# AY_Amp.net
KiCad netlist of a schematic drawn in Altium Designer
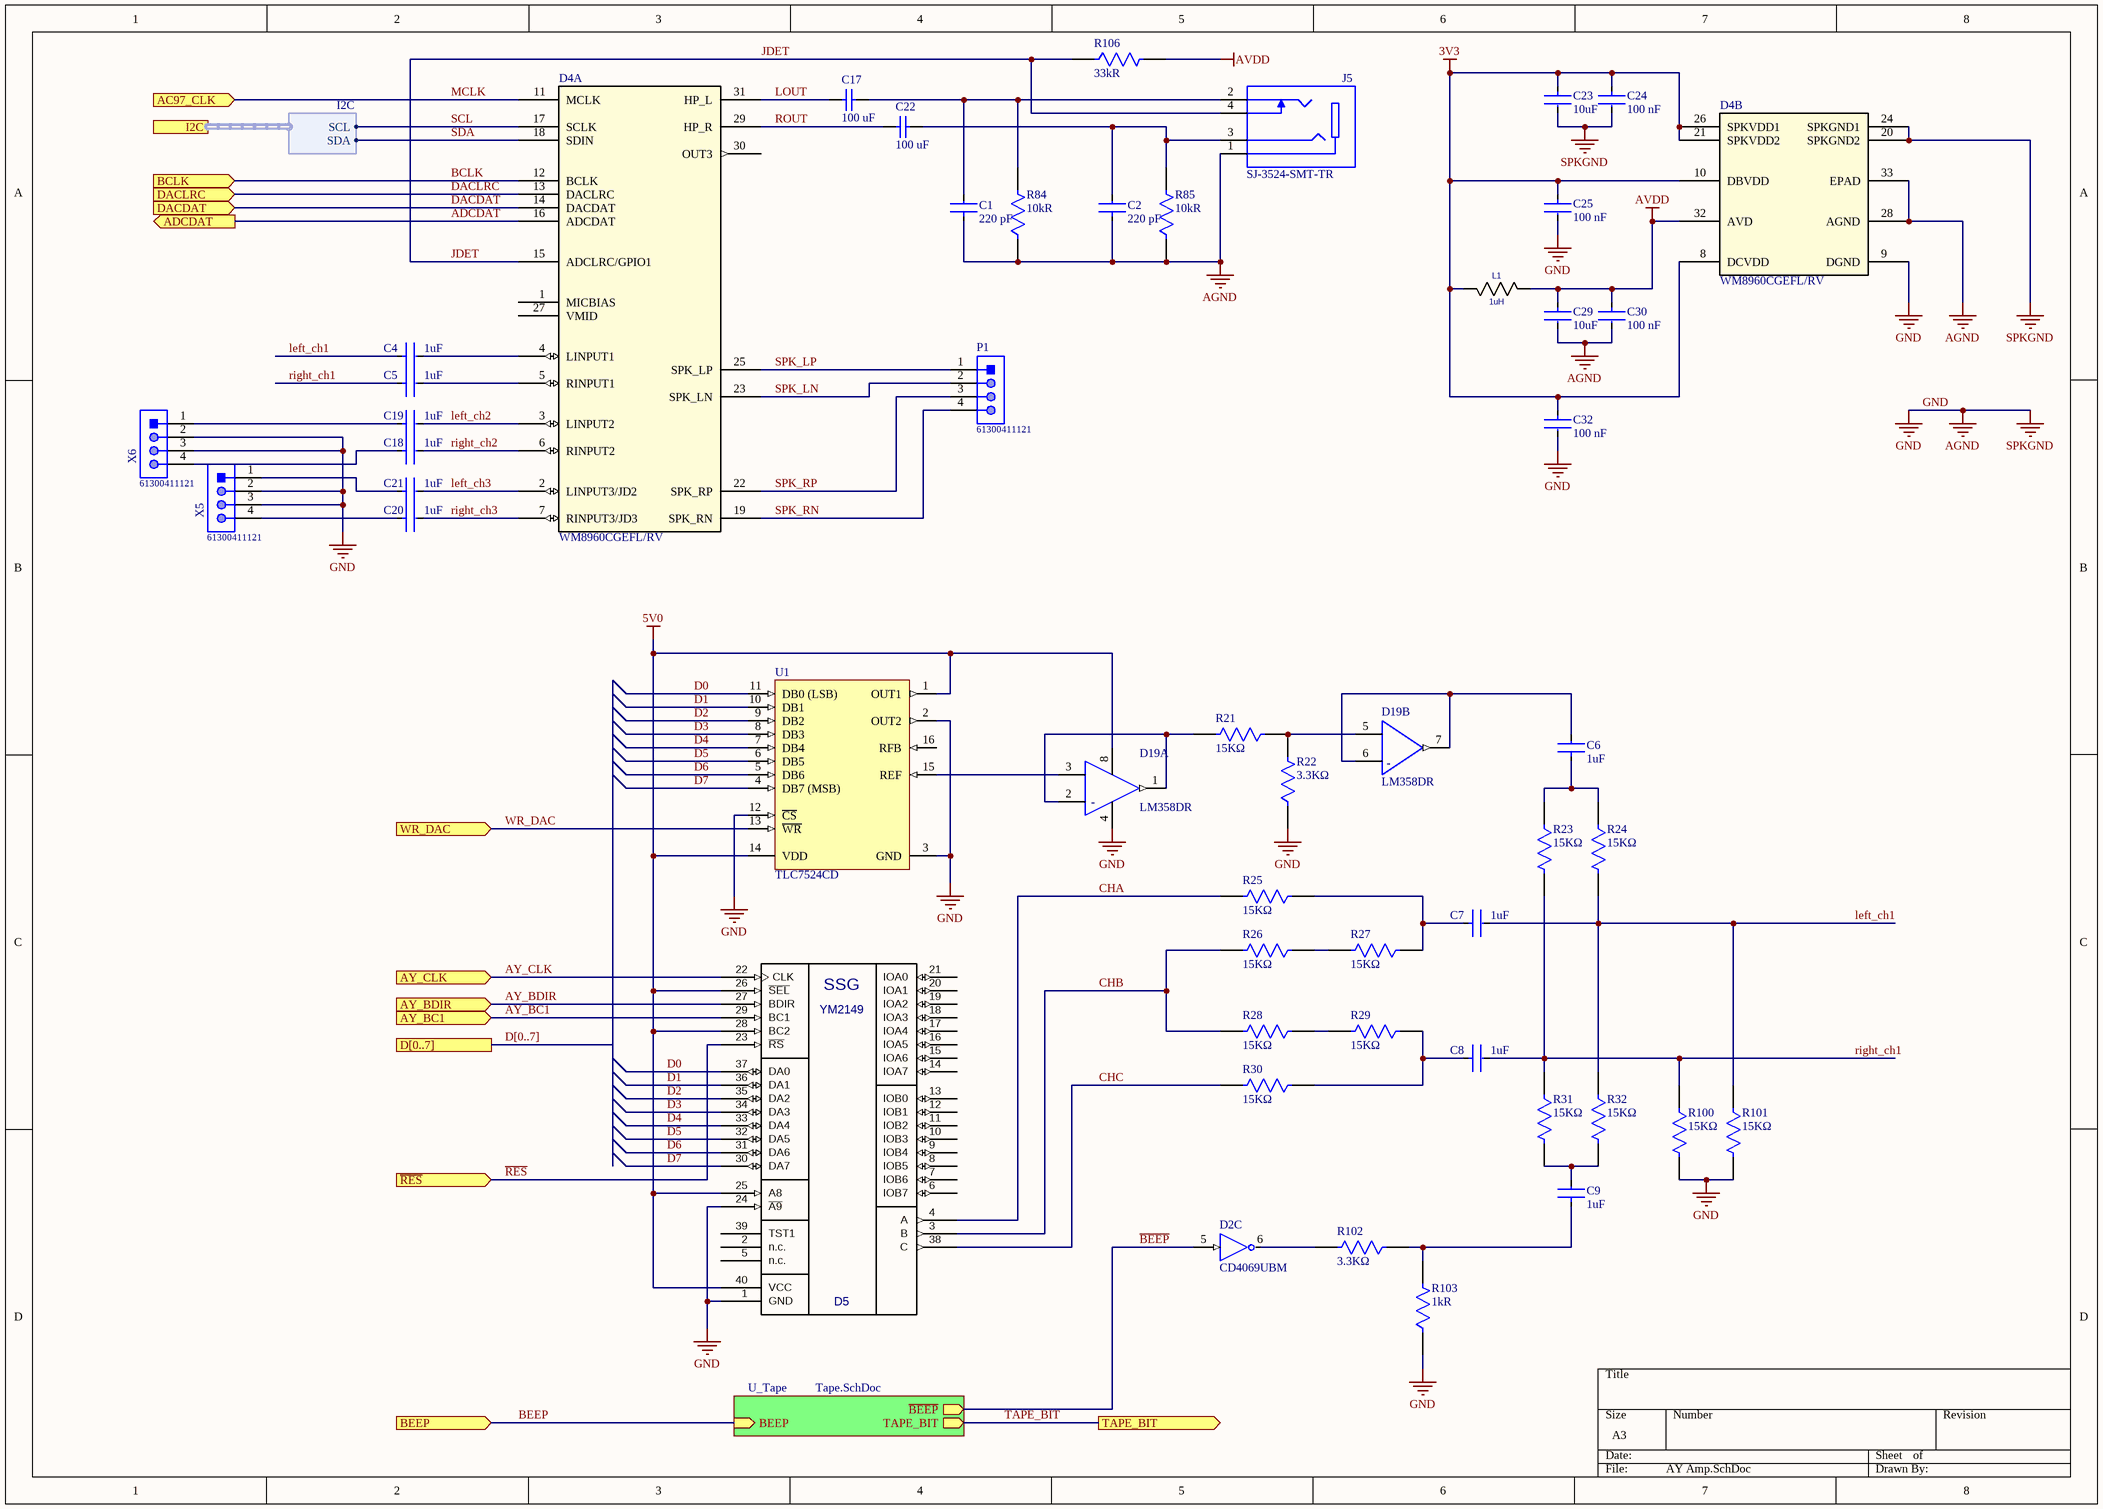
[diagram p0: AY Amp.SchDoc]

(export (version "E")
  (design (tool "Eeschema 10.0.6"))
  (components
    (comp (ref "C1")
      (value "CC0805KRX7R9BB221")
      (footprint "FP-CC0805-0_85-IPC_A")
      (description "CAP CER 220PF 50V X7R 0805")
      (fields
        (field (name "MANUFACTURER PART NUMBER") "VJ0805A221KXAPW1BC")
        (field (name "CAPACITANCE") "220 pF")
        (field (name "MANUFACTURER") "Vishay Vitramon")
      )
      (libsource (lib "SchLib") (part "CMP-1036-02315-3"))
    )
    (comp (ref "C2")
      (value "CC0805KRX7R9BB221")
      (footprint "FP-CC0805-0_85-IPC_A")
      (description "CAP CER 220PF 50V X7R 0805")
      (fields
        (field (name "MANUFACTURER PART NUMBER") "VJ0805A221KXAPW1BC")
        (field (name "CAPACITANCE") "220 pF")
        (field (name "MANUFACTURER") "Vishay Vitramon")
      )
      (libsource (lib "SchLib") (part "CMP-1036-02315-3"))
    )
    (comp (ref "C4")
      (value "GCM21BR71E105KA56L")
      (footprint "FP-GCM21B-0_15-IPC_A")
      (description "Ceramic Capacitor for Automotive 1uF ±10% 25VDC X7R 0805 Embossed T/R")
      (fields (field (name "CAPACITANCE") "1uF") (field (name "MANUFACTURER") "Murata"))
      (libsource (lib "SchLib") (part "CMP-2007-03346-2"))
    )
    (comp (ref "C5")
      (value "GCM21BR71E105KA56L")
      (footprint "FP-GCM21B-0_15-IPC_A")
      (description "Ceramic Capacitor for Automotive 1uF ±10% 25VDC X7R 0805 Embossed T/R")
      (fields (field (name "CAPACITANCE") "1uF") (field (name "MANUFACTURER") "Murata"))
      (libsource (lib "SchLib") (part "CMP-2007-03346-2"))
    )
    (comp (ref "C6")
      (value "GCM21BR71E105KA56L")
      (footprint "FP-GCM21B-0_15-IPC_A")
      (description "Ceramic Capacitor for Automotive 1uF ±10% 25VDC X7R 0805 Embossed T/R")
      (fields (field (name "CAPACITANCE") "1uF") (field (name "MANUFACTURER") "Murata"))
      (libsource (lib "SchLib") (part "CMP-2007-03346-2"))
    )
    (comp (ref "C7")
      (value "GCM21BR71E105KA56L")
      (footprint "FP-GCM21B-0_15-IPC_A")
      (description "Ceramic Capacitor for Automotive 1uF ±10% 25VDC X7R 0805 Embossed T/R")
      (fields (field (name "CAPACITANCE") "1uF") (field (name "MANUFACTURER") "Murata"))
      (libsource (lib "SchLib") (part "CMP-2007-03346-2"))
    )
    (comp (ref "C8")
      (value "GCM21BR71E105KA56L")
      (footprint "FP-GCM21B-0_15-IPC_A")
      (description "Ceramic Capacitor for Automotive 1uF ±10% 25VDC X7R 0805 Embossed T/R")
      (fields (field (name "CAPACITANCE") "1uF") (field (name "MANUFACTURER") "Murata"))
      (libsource (lib "SchLib") (part "CMP-2007-03346-2"))
    )
    (comp (ref "C9")
      (value "GCM21BR71E105KA56L")
      (footprint "FP-GCM21B-0_15-IPC_A")
      (description "Ceramic Capacitor for Automotive 1uF ±10% 25VDC X7R 0805 Embossed T/R")
      (fields (field (name "CAPACITANCE") "1uF") (field (name "MANUFACTURER") "Murata"))
      (libsource (lib "SchLib") (part "CMP-2007-03346-2"))
    )
    (comp (ref "C17")
      (value "GRM31CR60J107ME39L")
      (footprint "CAPC3216X190X55ML30T25")
      (description "Chip Capacitor, 100 uF, +/- 20%, 6.3 V, -55 to 85 degC, 1206 (3216 Metric), RoHS, Tape and Reel")
      (fields (field (name "CAPACITANCE") "100 uF") (field (name "MANUFACTURER") "Murata"))
      (libsource (lib "SchLib") (part "CMP-1662-00011-2"))
    )
    (comp (ref "C18")
      (value "GCM21BR71E105KA56L")
      (footprint "FP-GCM21B-0_15-IPC_A")
      (description "Ceramic Capacitor for Automotive 1uF ±10% 25VDC X7R 0805 Embossed T/R")
      (fields (field (name "CAPACITANCE") "1uF") (field (name "MANUFACTURER") "Murata"))
      (libsource (lib "SchLib") (part "CMP-2007-03346-2"))
    )
    (comp (ref "C19")
      (value "GCM21BR71E105KA56L")
      (footprint "FP-GCM21B-0_15-IPC_A")
      (description "Ceramic Capacitor for Automotive 1uF ±10% 25VDC X7R 0805 Embossed T/R")
      (fields (field (name "CAPACITANCE") "1uF") (field (name "MANUFACTURER") "Murata"))
      (libsource (lib "SchLib") (part "CMP-2007-03346-2"))
    )
    (comp (ref "C20")
      (value "GCM21BR71E105KA56L")
      (footprint "FP-GCM21B-0_15-IPC_A")
      (description "Ceramic Capacitor for Automotive 1uF ±10% 25VDC X7R 0805 Embossed T/R")
      (fields (field (name "CAPACITANCE") "1uF") (field (name "MANUFACTURER") "Murata"))
      (libsource (lib "SchLib") (part "CMP-2007-03346-2"))
    )
    (comp (ref "C21")
      (value "GCM21BR71E105KA56L")
      (footprint "FP-GCM21B-0_15-IPC_A")
      (description "Ceramic Capacitor for Automotive 1uF ±10% 25VDC X7R 0805 Embossed T/R")
      (fields (field (name "CAPACITANCE") "1uF") (field (name "MANUFACTURER") "Murata"))
      (libsource (lib "SchLib") (part "CMP-2007-03346-2"))
    )
    (comp (ref "C22")
      (value "GRM31CR60J107ME39L")
      (footprint "CAPC3216X190X55ML30T25")
      (description "Chip Capacitor, 100 uF, +/- 20%, 6.3 V, -55 to 85 degC, 1206 (3216 Metric), RoHS, Tape and Reel")
      (fields (field (name "CAPACITANCE") "100 uF") (field (name "MANUFACTURER") "Murata"))
      (libsource (lib "SchLib") (part "CMP-1662-00011-2"))
    )
    (comp (ref "C23")
      (value "C0805C106K8PACTU")
      (footprint "FP-C0805C-DG-IPC_A")
      (description "CAP CER 10UF 10V X5R 0805")
      (fields (field (name "MANUFACTURER") "KEMET") (field (name "CAPACITANCE") "10uF"))
      (libsource (lib "SchLib") (part "CMP-2007-03243-2"))
    )
    (comp (ref "C24")
      (value "CC0805KRX7R9BB104")
      (footprint "FP-CC0805-0_85-IPC_A")
      (description "CAP CER 0.1UF 50V X7R 0805")
      (fields (field (name "MANUFACTURER") "Yageo") (field (name "CAPACITANCE") "100 nF"))
      (libsource (lib "SchLib") (part "CMP-2100-03606-3"))
    )
    (comp (ref "C25")
      (value "CC0805KRX7R9BB104")
      (footprint "FP-CC0805-0_85-IPC_A")
      (description "CAP CER 0.1UF 50V X7R 0805")
      (fields (field (name "MANUFACTURER") "Yageo") (field (name "CAPACITANCE") "100 nF"))
      (libsource (lib "SchLib") (part "CMP-2100-03606-3"))
    )
    (comp (ref "C29")
      (value "C0805C106K8PACTU")
      (footprint "FP-C0805C-DG-IPC_A")
      (description "CAP CER 10UF 10V X5R 0805")
      (fields (field (name "MANUFACTURER") "KEMET") (field (name "CAPACITANCE") "10uF"))
      (libsource (lib "SchLib") (part "CMP-2007-03243-2"))
    )
    (comp (ref "C30")
      (value "CC0805KRX7R9BB104")
      (footprint "FP-CC0805-0_85-IPC_A")
      (description "CAP CER 0.1UF 50V X7R 0805")
      (fields (field (name "MANUFACTURER") "Yageo") (field (name "CAPACITANCE") "100 nF"))
      (libsource (lib "SchLib") (part "CMP-2100-03606-3"))
    )
    (comp (ref "C32")
      (value "CC0805KRX7R9BB104")
      (footprint "FP-CC0805-0_85-IPC_A")
      (description "CAP CER 0.1UF 50V X7R 0805")
      (fields (field (name "MANUFACTURER") "Yageo") (field (name "CAPACITANCE") "100 nF"))
      (libsource (lib "SchLib") (part "CMP-2100-03606-3"))
    )
    (comp (ref "D2")
      (value "CD4069UBM")
      (footprint "FP-D0014A-IPC_A")
      (description "IC INVERTER 6CH 6-INP 14SOIC")
      (fields (field (name "MANUFACTURER") "Texas Instruments"))
      (libsource (lib "SchLib") (part "CMP-1615-00195-3"))
    )
    (comp (ref "D4")
      (value "WM8960CGEFL/RV")
      (footprint "QFN50P500X500X90_HS-33M")
      (description "Stereo CODEC with 1W Stereo Class-D speaker Drivers")
      (libsource (lib "SchLib") (part "WM8960CGEFL/RV"))
    )
    (comp (ref "D5") (value "YM2149") (footprint "DIP40") (libsource (lib "SchLib") (part "YM2149")))
    (comp (ref "D19")
      (value "LM358DR")
      (footprint "FP-D0008A-MFG")
      (description "IC OPAMP GP 2 CIRCUIT 8SOIC")
      (fields (field (name "MANUFACTURER") "Texas Instruments"))
      (libsource (lib "SchLib") (part "CMP-1685-00009-2"))
    )
    (comp (ref "J5")
      (value "SJ-3524-SMT-TR")
      (footprint "SJ-3524-SMT-TR")
      (description "Connector")
      (libsource (lib "SchLib") (part "SJ-3524-SMT-TR"))
    )
    (comp (ref "L1")
      (value "1uH")
      (footprint "L-CHIP")
      (description "L-CHIP")
      (libsource (lib "SchLib") (part "L-CHIP"))
    )
    (comp (ref "P1")
      (value "61300411121")
      (footprint "61300411121")
      (description "THT Vertical Pin Header WR-PHD, Pitch 2.54 mm, Single Row, 4 pins")
      (fields (field (name "MANUFACTURER") "Wurth Electronics"))
      (libsource (lib "SchLib") (part "CMP-1502-01064-1"))
    )
    (comp (ref "R21")
      (value "RN73C2A15KBTDF")
      (footprint "FP-RN732A-IPC_A")
      (description "SMD Chip Resistor, Thin Film, 15KΩ, 100 V, 0805 [2012 Metric], 100 mW, 0.1%, RN73 Series")
      (fields (field (name "MANUFACTURER") "TE Connectivity") (field (name "RESISTANCE") "15KΩ"))
      (libsource (lib "SchLib") (part "CMP-03211-008328-1"))
    )
    (comp (ref "R22")
      (value "RT0805FRE073K3L")
      (footprint "FP-RT0805-IPC_A")
      (description "RES SMD 3.3K OHM 1% 1/8W 0805")
      (fields (field (name "MANUFACTURER") "Yageo") (field (name "RESISTANCE") "3.3KΩ"))
      (libsource (lib "SchLib") (part "CMP-03412-025935-1"))
    )
    (comp (ref "R23")
      (value "RN73C2A15KBTDF")
      (footprint "FP-RN732A-IPC_A")
      (description "SMD Chip Resistor, Thin Film, 15KΩ, 100 V, 0805 [2012 Metric], 100 mW, 0.1%, RN73 Series")
      (fields (field (name "MANUFACTURER") "TE Connectivity") (field (name "RESISTANCE") "15KΩ"))
      (libsource (lib "SchLib") (part "CMP-03211-008328-1"))
    )
    (comp (ref "R24")
      (value "RN73C2A15KBTDF")
      (footprint "FP-RN732A-IPC_A")
      (description "SMD Chip Resistor, Thin Film, 15KΩ, 100 V, 0805 [2012 Metric], 100 mW, 0.1%, RN73 Series")
      (fields (field (name "MANUFACTURER") "TE Connectivity") (field (name "RESISTANCE") "15KΩ"))
      (libsource (lib "SchLib") (part "CMP-03211-008328-1"))
    )
    (comp (ref "R25")
      (value "RN73C2A15KBTDF")
      (footprint "FP-RN732A-IPC_A")
      (description "SMD Chip Resistor, Thin Film, 15KΩ, 100 V, 0805 [2012 Metric], 100 mW, 0.1%, RN73 Series")
      (fields (field (name "MANUFACTURER") "TE Connectivity") (field (name "RESISTANCE") "15KΩ"))
      (libsource (lib "SchLib") (part "CMP-03211-008328-1"))
    )
    (comp (ref "R26")
      (value "RN73C2A15KBTDF")
      (footprint "FP-RN732A-IPC_A")
      (description "SMD Chip Resistor, Thin Film, 15KΩ, 100 V, 0805 [2012 Metric], 100 mW, 0.1%, RN73 Series")
      (fields (field (name "MANUFACTURER") "TE Connectivity") (field (name "RESISTANCE") "15KΩ"))
      (libsource (lib "SchLib") (part "CMP-03211-008328-1"))
    )
    (comp (ref "R27")
      (value "RN73C2A15KBTDF")
      (footprint "FP-RN732A-IPC_A")
      (description "SMD Chip Resistor, Thin Film, 15KΩ, 100 V, 0805 [2012 Metric], 100 mW, 0.1%, RN73 Series")
      (fields (field (name "MANUFACTURER") "TE Connectivity") (field (name "RESISTANCE") "15KΩ"))
      (libsource (lib "SchLib") (part "CMP-03211-008328-1"))
    )
    (comp (ref "R28")
      (value "RN73C2A15KBTDF")
      (footprint "FP-RN732A-IPC_A")
      (description "SMD Chip Resistor, Thin Film, 15KΩ, 100 V, 0805 [2012 Metric], 100 mW, 0.1%, RN73 Series")
      (fields (field (name "MANUFACTURER") "TE Connectivity") (field (name "RESISTANCE") "15KΩ"))
      (libsource (lib "SchLib") (part "CMP-03211-008328-1"))
    )
    (comp (ref "R29")
      (value "RN73C2A15KBTDF")
      (footprint "FP-RN732A-IPC_A")
      (description "SMD Chip Resistor, Thin Film, 15KΩ, 100 V, 0805 [2012 Metric], 100 mW, 0.1%, RN73 Series")
      (fields (field (name "MANUFACTURER") "TE Connectivity") (field (name "RESISTANCE") "15KΩ"))
      (libsource (lib "SchLib") (part "CMP-03211-008328-1"))
    )
    (comp (ref "R30")
      (value "RN73C2A15KBTDF")
      (footprint "FP-RN732A-IPC_A")
      (description "SMD Chip Resistor, Thin Film, 15KΩ, 100 V, 0805 [2012 Metric], 100 mW, 0.1%, RN73 Series")
      (fields (field (name "MANUFACTURER") "TE Connectivity") (field (name "RESISTANCE") "15KΩ"))
      (libsource (lib "SchLib") (part "CMP-03211-008328-1"))
    )
    (comp (ref "R31")
      (value "RN73C2A15KBTDF")
      (footprint "FP-RN732A-IPC_A")
      (description "SMD Chip Resistor, Thin Film, 15KΩ, 100 V, 0805 [2012 Metric], 100 mW, 0.1%, RN73 Series")
      (fields (field (name "MANUFACTURER") "TE Connectivity") (field (name "RESISTANCE") "15KΩ"))
      (libsource (lib "SchLib") (part "CMP-03211-008328-1"))
    )
    (comp (ref "R32")
      (value "RN73C2A15KBTDF")
      (footprint "FP-RN732A-IPC_A")
      (description "SMD Chip Resistor, Thin Film, 15KΩ, 100 V, 0805 [2012 Metric], 100 mW, 0.1%, RN73 Series")
      (fields (field (name "MANUFACTURER") "TE Connectivity") (field (name "RESISTANCE") "15KΩ"))
      (libsource (lib "SchLib") (part "CMP-03211-008328-1"))
    )
    (comp (ref "R84")
      (value "CR0805-JW-103ELF")
      (footprint "FP-CR0805-IPC_A")
      (description "Thick Film Chip Resistors 0805 10kΩ 0.125W 5% 200ppm/°C")
      (fields (field (name "RESISTANCE") "10kR") (field (name "MANUFACTURER") "Bourns"))
      (libsource (lib "SchLib") (part "CMP-07231-003873-1"))
    )
    (comp (ref "R85")
      (value "CR0805-JW-103ELF")
      (footprint "FP-CR0805-IPC_A")
      (description "Thick Film Chip Resistors 0805 10kΩ 0.125W 5% 200ppm/°C")
      (fields (field (name "RESISTANCE") "10kR") (field (name "MANUFACTURER") "Bourns"))
      (libsource (lib "SchLib") (part "CMP-07231-003873-1"))
    )
    (comp (ref "R100")
      (value "RN73C2A15KBTDF")
      (footprint "FP-RN732A-IPC_A")
      (description "SMD Chip Resistor, Thin Film, 15KΩ, 100 V, 0805 [2012 Metric], 100 mW, 0.1%, RN73 Series")
      (fields (field (name "MANUFACTURER") "TE Connectivity") (field (name "RESISTANCE") "15KΩ"))
      (libsource (lib "SchLib") (part "CMP-03211-008328-1"))
    )
    (comp (ref "R101")
      (value "RN73C2A15KBTDF")
      (footprint "FP-RN732A-IPC_A")
      (description "SMD Chip Resistor, Thin Film, 15KΩ, 100 V, 0805 [2012 Metric], 100 mW, 0.1%, RN73 Series")
      (fields (field (name "MANUFACTURER") "TE Connectivity") (field (name "RESISTANCE") "15KΩ"))
      (libsource (lib "SchLib") (part "CMP-03211-008328-1"))
    )
    (comp (ref "R102")
      (value "RT0805FRE073K3L")
      (footprint "FP-RT0805-IPC_A")
      (description "RES SMD 3.3K OHM 1% 1/8W 0805")
      (fields (field (name "MANUFACTURER") "Yageo") (field (name "RESISTANCE") "3.3KΩ"))
      (libsource (lib "SchLib") (part "CMP-03412-025935-1"))
    )
    (comp (ref "R103")
      (value "CRCW08051K00FKEAHP")
      (footprint "FP-CRCW0805-HPe3-IPC_A")
      (description "RES Thick Film, 1kΩ, 1%, 0.5W, 100ppm/°C, 0805")
      (fields (field (name "RESISTANCE") "1kR") (field (name "MANUFACTURER") "Vishay Dale"))
      (libsource (lib "SchLib") (part "CMP-02407-004529-1"))
    )
    (comp (ref "R106")
      (value "RMCF0805JT33K0")
      (footprint "FP-RMCF0805-IPC_A")
      (description "33kΩ ±5% 0.125W 0805 Thick Film Chip Resistor AEC-Q200 compliant")
      (fields (field (name "RESISTANCE") "33kR") (field (name "MANUFACTURER") "Stackpole Electronics"))
      (libsource (lib "SchLib") (part "CMP-26527-001097-1"))
    )
    (comp (ref "U1")
      (value "TLC7524CD")
      (footprint "TI-D16_N")
      (fields (field (name "MANUFACTURER") "Texas Instruments"))
      (libsource (lib "SchLib") (part "CMP-0004-00046-1"))
    )
    (comp (ref "X5")
      (value "61300411121")
      (footprint "61300411121")
      (description "THT Vertical Pin Header WR-PHD, Pitch 2.54 mm, Single Row, 4 pins")
      (fields (field (name "MANUFACTURER") "Wurth Electronics"))
      (libsource (lib "") (part "CMP-1502-01064-1_1"))
    )
    (comp (ref "X6")
      (value "61300411121")
      (footprint "61300411121")
      (description "THT Vertical Pin Header WR-PHD, Pitch 2.54 mm, Single Row, 4 pins")
      (fields (field (name "MANUFACTURER") "Wurth Electronics"))
      (libsource (lib "") (part "CMP-1502-01064-1_1"))
    )
  )
  (nets
    (net (code "2") (name "/ADCDAT") (class "Default")
      (node (ref "D4") (pin "16") (pinfunction "ADCDAT_16") (pintype "passive"))
    )
    (net (code "3") (name "/AY_BC1") (class "Default")
      (node (ref "D5") (pin "29") (pinfunction "BC1_29") (pintype "input"))
    )
    (net (code "4") (name "/AY_BDIR") (class "Default")
      (node (ref "D5") (pin "27") (pinfunction "BDIR_27") (pintype "input"))
    )
    (net (code "5") (name "/AY_CLK") (class "Default")
      (node (ref "D5") (pin "22") (pinfunction "CLK_22") (pintype "input"))
    )
    (net (code "6") (name "/BCLK") (class "Default")
      (node (ref "D4") (pin "12") (pinfunction "BCLK_12") (pintype "passive"))
    )
    (net (code "8") (name "/CHA") (class "Default")
      (node (ref "D5") (pin "4") (pinfunction "A_4") (pintype "output"))
      (node (ref "R25") (pin "2") (pinfunction "2_2") (pintype "passive"))
    )
    (net (code "9") (name "/CHB") (class "Default")
      (node (ref "D5") (pin "3") (pinfunction "B_3") (pintype "output"))
      (node (ref "R26") (pin "2") (pinfunction "2_2") (pintype "passive"))
      (node (ref "R28") (pin "2") (pinfunction "2_2") (pintype "passive"))
    )
    (net (code "10") (name "/CHC") (class "Default")
      (node (ref "D5") (pin "38") (pinfunction "C_38") (pintype "output"))
      (node (ref "R30") (pin "2") (pinfunction "2_2") (pintype "passive"))
    )
    (net (code "11") (name "/D0") (class "Default")
      (node (ref "D5") (pin "37") (pinfunction "DA0_37") (pintype "bidirectional"))
      (node (ref "U1") (pin "11") (pinfunction "DB0_(LSB)_11") (pintype "input"))
    )
    (net (code "12") (name "/D1") (class "Default")
      (node (ref "D5") (pin "36") (pinfunction "DA1_36") (pintype "bidirectional"))
      (node (ref "U1") (pin "10") (pinfunction "DB1_10") (pintype "input"))
    )
    (net (code "13") (name "/D2") (class "Default")
      (node (ref "D5") (pin "35") (pinfunction "DA2_35") (pintype "bidirectional"))
      (node (ref "U1") (pin "9") (pinfunction "DB2_9") (pintype "input"))
    )
    (net (code "14") (name "/D3") (class "Default")
      (node (ref "D5") (pin "34") (pinfunction "DA3_34") (pintype "bidirectional"))
      (node (ref "U1") (pin "8") (pinfunction "DB3_8") (pintype "input"))
    )
    (net (code "15") (name "/D4") (class "Default")
      (node (ref "D5") (pin "33") (pinfunction "DA4_33") (pintype "bidirectional"))
      (node (ref "U1") (pin "7") (pinfunction "DB4_7") (pintype "input"))
    )
    (net (code "16") (name "/D5") (class "Default")
      (node (ref "D5") (pin "32") (pinfunction "DA5_32") (pintype "bidirectional"))
      (node (ref "U1") (pin "6") (pinfunction "DB5_6") (pintype "input"))
    )
    (net (code "17") (name "/D6") (class "Default")
      (node (ref "D5") (pin "31") (pinfunction "DA6_31") (pintype "bidirectional"))
      (node (ref "U1") (pin "5") (pinfunction "DB6_5") (pintype "input"))
    )
    (net (code "18") (name "/D7") (class "Default")
      (node (ref "D5") (pin "30") (pinfunction "DA7_30") (pintype "bidirectional"))
      (node (ref "U1") (pin "4") (pinfunction "DB7_(MSB)_4") (pintype "input"))
    )
    (net (code "19") (name "/DACDAT") (class "Default")
      (node (ref "D4") (pin "14") (pinfunction "DACDAT_14") (pintype "passive"))
    )
    (net (code "20") (name "/DACLRC") (class "Default")
      (node (ref "D4") (pin "13") (pinfunction "DACLRC_13") (pintype "passive"))
    )
    (net (code "22") (name "/JDET") (class "Default")
      (node (ref "D4") (pin "15") (pinfunction "ADCLRC/GPIO1_15") (pintype "passive"))
      (node (ref "J5") (pin "4") (pinfunction "4_4") (pintype "passive"))
      (node (ref "R106") (pin "1") (pinfunction "1_1") (pintype "passive"))
    )
    (net (code "23") (name "/LOUT") (class "Default")
      (node (ref "C17") (pin "1") (pinfunction "1_1") (pintype "passive"))
      (node (ref "D4") (pin "31") (pinfunction "HP_L_31") (pintype "passive"))
    )
    (net (code "24") (name "/MCLK") (class "Default")
      (node (ref "D4") (pin "11") (pinfunction "MCLK_11") (pintype "passive"))
    )
    (net (code "25") (name "/ROUT") (class "Default")
      (node (ref "C22") (pin "1") (pinfunction "1_1") (pintype "passive"))
      (node (ref "D4") (pin "29") (pinfunction "HP_R_29") (pintype "passive"))
    )
    (net (code "26") (name "/SCL") (class "Default")
      (node (ref "D4") (pin "17") (pinfunction "SCLK_17") (pintype "passive"))
    )
    (net (code "27") (name "/SDA") (class "Default")
      (node (ref "D4") (pin "18") (pinfunction "SDIN_18") (pintype "passive"))
    )
    (net (code "28") (name "/SPK_LN") (class "Default")
      (node (ref "D4") (pin "23") (pinfunction "SPK_LN_23") (pintype "passive"))
      (node (ref "P1") (pin "2") (pinfunction "2_2") (pintype "passive"))
    )
    (net (code "29") (name "/SPK_LP") (class "Default")
      (node (ref "D4") (pin "25") (pinfunction "SPK_LP_25") (pintype "passive"))
      (node (ref "P1") (pin "1") (pinfunction "1_1") (pintype "passive"))
    )
    (net (code "30") (name "/SPK_RN") (class "Default")
      (node (ref "D4") (pin "19") (pinfunction "SPK_RN_19") (pintype "passive"))
      (node (ref "P1") (pin "4") (pinfunction "4_4") (pintype "passive"))
    )
    (net (code "31") (name "/SPK_RP") (class "Default")
      (node (ref "D4") (pin "22") (pinfunction "SPK_RP_22") (pintype "passive"))
      (node (ref "P1") (pin "3") (pinfunction "3_3") (pintype "passive"))
    )
    (net (code "33") (name "/WR_DAC") (class "Default")
      (node (ref "U1") (pin "13") (pinfunction "~{WR}_13") (pintype "input"))
    )
    (net (code "34") (name "/left_ch1") (class "Default")
      (node (ref "C4") (pin "1") (pinfunction "1_1") (pintype "passive"))
      (node (ref "C7") (pin "2") (pinfunction "2_2") (pintype "passive"))
      (node (ref "R101") (pin "1") (pinfunction "1_1") (pintype "passive"))
      (node (ref "R24") (pin "2") (pinfunction "2_2") (pintype "passive"))
      (node (ref "R32") (pin "1") (pinfunction "1_1") (pintype "passive"))
    )
    (net (code "35") (name "/left_ch2") (class "Default")
      (node (ref "C19") (pin "2") (pinfunction "2_2") (pintype "passive"))
      (node (ref "D4") (pin "3") (pinfunction "LINPUT2_3") (pintype "bidirectional"))
    )
    (net (code "36") (name "/left_ch3") (class "Default")
      (node (ref "C21") (pin "2") (pinfunction "2_2") (pintype "passive"))
      (node (ref "D4") (pin "2") (pinfunction "LINPUT3/JD2_2") (pintype "bidirectional"))
    )
    (net (code "37") (name "/right_ch1") (class "Default")
      (node (ref "C5") (pin "1") (pinfunction "1_1") (pintype "passive"))
      (node (ref "C8") (pin "2") (pinfunction "2_2") (pintype "passive"))
      (node (ref "R100") (pin "1") (pinfunction "1_1") (pintype "passive"))
      (node (ref "R23") (pin "2") (pinfunction "2_2") (pintype "passive"))
      (node (ref "R31") (pin "1") (pinfunction "1_1") (pintype "passive"))
    )
    (net (code "38") (name "/right_ch2") (class "Default")
      (node (ref "C18") (pin "2") (pinfunction "2_2") (pintype "passive"))
      (node (ref "D4") (pin "6") (pinfunction "RINPUT2_6") (pintype "bidirectional"))
    )
    (net (code "39") (name "/right_ch3") (class "Default")
      (node (ref "C20") (pin "2") (pinfunction "2_2") (pintype "passive"))
      (node (ref "D4") (pin "7") (pinfunction "RINPUT3/JD3_7") (pintype "bidirectional"))
    )
    (net (code "41") (name "/~{BEEP}") (class "Default")
      (node (ref "D2") (pin "5") (pinfunction "C_5") (pintype "input"))
    )
    (net (code "42") (name "/~{RES}") (class "Default")
      (node (ref "D5") (pin "23") (pinfunction "~{RS}_23") (pintype "input"))
    )
    (net (code "43") (name "3V3") (class "Default")
      (node (ref "C23") (pin "1") (pinfunction "1_1") (pintype "passive"))
      (node (ref "C24") (pin "1") (pinfunction "1_1") (pintype "passive"))
      (node (ref "C25") (pin "1") (pinfunction "1_1") (pintype "passive"))
      (node (ref "C32") (pin "1") (pinfunction "1_1") (pintype "passive"))
      (node (ref "D4") (pin "10") (pinfunction "DBVDD_10") (pintype "power_in"))
      (node (ref "D4") (pin "21") (pinfunction "SPKVDD2_21") (pintype "power_in"))
      (node (ref "D4") (pin "26") (pinfunction "SPKVDD1_26") (pintype "power_in"))
      (node (ref "D4") (pin "8") (pinfunction "DCVDD_8") (pintype "power_in"))
      (node (ref "L1") (pin "2") (pintype "passive"))
    )
    (net (code "44") (name "5V0") (class "Default")
      (node (ref "D19") (pin "8") (pinfunction "V+_8") (pintype "power_in"))
      (node (ref "D5") (pin "25") (pinfunction "A8_25") (pintype "input"))
      (node (ref "D5") (pin "26") (pinfunction "~{SEL}_26") (pintype "input"))
      (node (ref "D5") (pin "28") (pinfunction "BC2_28") (pintype "input"))
      (node (ref "D5") (pin "40") (pinfunction "VCC_40") (pintype "power_in"))
      (node (ref "U1") (pin "1") (pinfunction "OUT1_1") (pintype "output"))
      (node (ref "U1") (pin "14") (pinfunction "VDD_14") (pintype "power_in"))
    )
    (net (code "45") (name "AGND") (class "Default")
      (node (ref "C1") (pin "1") (pinfunction "1_1") (pintype "passive"))
      (node (ref "C2") (pin "1") (pinfunction "1_1") (pintype "passive"))
      (node (ref "C23") (pin "2") (pinfunction "2_2") (pintype "passive"))
      (node (ref "C24") (pin "2") (pinfunction "2_2") (pintype "passive"))
      (node (ref "C25") (pin "2") (pinfunction "2_2") (pintype "passive"))
      (node (ref "C29") (pin "2") (pinfunction "2_2") (pintype "passive"))
      (node (ref "C30") (pin "2") (pinfunction "2_2") (pintype "passive"))
      (node (ref "C32") (pin "2") (pinfunction "2_2") (pintype "passive"))
      (node (ref "D19") (pin "4") (pinfunction "V-_4") (pintype "power_in"))
      (node (ref "D4") (pin "20") (pinfunction "SPKGND2_20") (pintype "passive"))
      (node (ref "D4") (pin "24") (pinfunction "SPKGND1_24") (pintype "passive"))
      (node (ref "D4") (pin "28") (pinfunction "AGND_28") (pintype "passive"))
      (node (ref "D4") (pin "33") (pinfunction "EPAD_33") (pintype "passive"))
      (node (ref "D4") (pin "9") (pinfunction "DGND_9") (pintype "passive"))
      (node (ref "D5") (pin "1") (pinfunction "GND_1") (pintype "power_in"))
      (node (ref "D5") (pin "24") (pinfunction "~{A9}_24") (pintype "input"))
      (node (ref "J5") (pin "1") (pinfunction "1_1") (pintype "passive"))
      (node (ref "R100") (pin "2") (pinfunction "2_2") (pintype "passive"))
      (node (ref "R101") (pin "2") (pinfunction "2_2") (pintype "passive"))
      (node (ref "R103") (pin "1") (pinfunction "1_1") (pintype "passive"))
      (node (ref "R22") (pin "1") (pinfunction "1_1") (pintype "passive"))
      (node (ref "R84") (pin "1") (pinfunction "1_1") (pintype "passive"))
      (node (ref "R85") (pin "1") (pinfunction "1_1") (pintype "passive"))
      (node (ref "U1") (pin "12") (pinfunction "~{CS}_12") (pintype "input"))
      (node (ref "U1") (pin "2") (pinfunction "OUT2_2") (pintype "output"))
      (node (ref "U1") (pin "3") (pinfunction "GND_3") (pintype "power_in"))
      (node (ref "X5") (pin "2") (pinfunction "2_2") (pintype "passive"))
      (node (ref "X5") (pin "3") (pinfunction "3_3") (pintype "passive"))
      (node (ref "X6") (pin "2") (pinfunction "2_2") (pintype "passive"))
      (node (ref "X6") (pin "3") (pinfunction "3_3") (pintype "passive"))
    )
    (net (code "46") (name "AVDD") (class "Default")
      (node (ref "C29") (pin "1") (pinfunction "1_1") (pintype "passive"))
      (node (ref "C30") (pin "1") (pinfunction "1_1") (pintype "passive"))
      (node (ref "D4") (pin "32") (pinfunction "AVD_32") (pintype "passive"))
      (node (ref "L1") (pin "1") (pintype "passive"))
      (node (ref "R106") (pin "2") (pinfunction "2_2") (pintype "passive"))
    )
    (net (code "47") (name "Net-(C1-Pad2)") (class "Default")
      (node (ref "C1") (pin "2") (pinfunction "2_2") (pintype "passive"))
      (node (ref "C17") (pin "2") (pinfunction "2_2") (pintype "passive"))
      (node (ref "J5") (pin "2") (pinfunction "2_2") (pintype "passive"))
      (node (ref "R84") (pin "2") (pinfunction "2_2") (pintype "passive"))
    )
    (net (code "48") (name "Net-(C2-Pad2)") (class "Default")
      (node (ref "C2") (pin "2") (pinfunction "2_2") (pintype "passive"))
      (node (ref "C22") (pin "2") (pinfunction "2_2") (pintype "passive"))
      (node (ref "J5") (pin "3") (pinfunction "3_3") (pintype "passive"))
      (node (ref "R85") (pin "2") (pinfunction "2_2") (pintype "passive"))
    )
    (net (code "49") (name "Net-(C6-Pad1)") (class "Default")
      (node (ref "C6") (pin "1") (pinfunction "1_1") (pintype "passive"))
      (node (ref "R23") (pin "1") (pinfunction "1_1") (pintype "passive"))
      (node (ref "R24") (pin "1") (pinfunction "1_1") (pintype "passive"))
    )
    (net (code "50") (name "Net-(C7-Pad1)") (class "Default")
      (node (ref "C7") (pin "1") (pinfunction "1_1") (pintype "passive"))
      (node (ref "R25") (pin "1") (pinfunction "1_1") (pintype "passive"))
      (node (ref "R27") (pin "1") (pinfunction "1_1") (pintype "passive"))
    )
    (net (code "51") (name "Net-(C8-Pad1)") (class "Default")
      (node (ref "C8") (pin "1") (pinfunction "1_1") (pintype "passive"))
      (node (ref "R29") (pin "1") (pinfunction "1_1") (pintype "passive"))
      (node (ref "R30") (pin "1") (pinfunction "1_1") (pintype "passive"))
    )
    (net (code "52") (name "Net-(C9-Pad1)") (class "Default")
      (node (ref "C9") (pin "1") (pinfunction "1_1") (pintype "passive"))
      (node (ref "R102") (pin "1") (pinfunction "1_1") (pintype "passive"))
      (node (ref "R103") (pin "2") (pinfunction "2_2") (pintype "passive"))
    )
    (net (code "53") (name "Net-(C9-Pad2)") (class "Default")
      (node (ref "C9") (pin "2") (pinfunction "2_2") (pintype "passive"))
      (node (ref "R31") (pin "2") (pinfunction "2_2") (pintype "passive"))
      (node (ref "R32") (pin "2") (pinfunction "2_2") (pintype "passive"))
    )
    (net (code "54") (name "Net-(C18-Pad1)") (class "Default")
      (node (ref "C18") (pin "1") (pinfunction "1_1") (pintype "passive"))
      (node (ref "X6") (pin "4") (pinfunction "4_4") (pintype "passive"))
    )
    (net (code "55") (name "Net-(C19-Pad1)") (class "Default")
      (node (ref "C19") (pin "1") (pinfunction "1_1") (pintype "passive"))
      (node (ref "X6") (pin "1") (pinfunction "1_1") (pintype "passive"))
    )
    (net (code "56") (name "Net-(C20-Pad1)") (class "Default")
      (node (ref "C20") (pin "1") (pinfunction "1_1") (pintype "passive"))
      (node (ref "X5") (pin "4") (pinfunction "4_4") (pintype "passive"))
    )
    (net (code "57") (name "Net-(C21-Pad1)") (class "Default")
      (node (ref "C21") (pin "1") (pinfunction "1_1") (pintype "passive"))
      (node (ref "X5") (pin "1") (pinfunction "1_1") (pintype "passive"))
    )
    (net (code "58") (name "Net-(D2C-~{C})") (class "Default")
      (node (ref "D2") (pin "6") (pinfunction "~{C}_6") (pintype "output"))
      (node (ref "R102") (pin "2") (pinfunction "2_2") (pintype "passive"))
    )
    (net (code "59") (name "Net-(D4A-LINPUT1)") (class "Default")
      (node (ref "C4") (pin "2") (pinfunction "2_2") (pintype "passive"))
      (node (ref "D4") (pin "4") (pinfunction "LINPUT1_4") (pintype "bidirectional"))
    )
    (net (code "60") (name "Net-(D4A-RINPUT1)") (class "Default")
      (node (ref "C5") (pin "2") (pinfunction "2_2") (pintype "passive"))
      (node (ref "D4") (pin "5") (pinfunction "RINPUT1_5") (pintype "bidirectional"))
    )
    (net (code "61") (name "Net-(D19A-1OUT)") (class "Default")
      (node (ref "D19") (pin "1") (pinfunction "1OUT_1") (pintype "output"))
      (node (ref "D19") (pin "2") (pinfunction "IN1-_2") (pintype "tri_state"))
      (node (ref "R21") (pin "2") (pinfunction "2_2") (pintype "passive"))
    )
    (net (code "62") (name "Net-(D19A-IN1+)") (class "Default")
      (node (ref "D19") (pin "3") (pinfunction "IN1+_3") (pintype "tri_state"))
      (node (ref "U1") (pin "15") (pinfunction "REF_15") (pintype "input"))
    )
    (net (code "63") (name "Net-(D19B-2OUT)") (class "Default")
      (node (ref "C6") (pin "2") (pinfunction "2_2") (pintype "passive"))
      (node (ref "D19") (pin "6") (pinfunction "IN2-_6") (pintype "tri_state"))
      (node (ref "D19") (pin "7") (pinfunction "2OUT_7") (pintype "output"))
    )
    (net (code "64") (name "Net-(D19B-IN2+)") (class "Default")
      (node (ref "D19") (pin "5") (pinfunction "IN2+_5") (pintype "tri_state"))
      (node (ref "R21") (pin "1") (pinfunction "1_1") (pintype "passive"))
      (node (ref "R22") (pin "2") (pinfunction "2_2") (pintype "passive"))
    )
    (net (code "65") (name "Net-(R26-Pad1)") (class "Default")
      (node (ref "R26") (pin "1") (pinfunction "1_1") (pintype "passive"))
      (node (ref "R27") (pin "2") (pinfunction "2_2") (pintype "passive"))
    )
    (net (code "66") (name "Net-(R28-Pad1)") (class "Default")
      (node (ref "R28") (pin "1") (pinfunction "1_1") (pintype "passive"))
      (node (ref "R29") (pin "2") (pinfunction "2_2") (pintype "passive"))
    )
    (net (code "67") (name "unconnected-(D4A-MICBIAS-Pad1)") (class "Default")
      (node (ref "D4") (pin "1") (pinfunction "MICBIAS_1") (pintype "passive"))
    )
    (net (code "68") (name "unconnected-(D4A-OUT3-Pad30)") (class "Default")
      (node (ref "D4") (pin "30") (pinfunction "OUT3_30") (pintype "output"))
    )
    (net (code "69") (name "unconnected-(D4A-VMID-Pad27)") (class "Default")
      (node (ref "D4") (pin "27") (pinfunction "VMID_27") (pintype "passive"))
    )
    (net (code "70") (name "unconnected-(D5-IOA0-Pad21)") (class "Default")
      (node (ref "D5") (pin "21") (pinfunction "IOA0_21") (pintype "bidirectional"))
    )
    (net (code "71") (name "unconnected-(D5-IOA1-Pad20)") (class "Default")
      (node (ref "D5") (pin "20") (pinfunction "IOA1_20") (pintype "bidirectional"))
    )
    (net (code "72") (name "unconnected-(D5-IOA2-Pad19)") (class "Default")
      (node (ref "D5") (pin "19") (pinfunction "IOA2_19") (pintype "bidirectional"))
    )
    (net (code "73") (name "unconnected-(D5-IOA3-Pad18)") (class "Default")
      (node (ref "D5") (pin "18") (pinfunction "IOA3_18") (pintype "bidirectional"))
    )
    (net (code "74") (name "unconnected-(D5-IOA4-Pad17)") (class "Default")
      (node (ref "D5") (pin "17") (pinfunction "IOA4_17") (pintype "bidirectional"))
    )
    (net (code "75") (name "unconnected-(D5-IOA5-Pad16)") (class "Default")
      (node (ref "D5") (pin "16") (pinfunction "IOA5_16") (pintype "bidirectional"))
    )
    (net (code "76") (name "unconnected-(D5-IOA6-Pad15)") (class "Default")
      (node (ref "D5") (pin "15") (pinfunction "IOA6_15") (pintype "bidirectional"))
    )
    (net (code "77") (name "unconnected-(D5-IOA7-Pad14)") (class "Default")
      (node (ref "D5") (pin "14") (pinfunction "IOA7_14") (pintype "bidirectional"))
    )
    (net (code "78") (name "unconnected-(D5-IOB0-Pad13)") (class "Default")
      (node (ref "D5") (pin "13") (pinfunction "IOB0_13") (pintype "bidirectional"))
    )
    (net (code "79") (name "unconnected-(D5-IOB1-Pad12)") (class "Default")
      (node (ref "D5") (pin "12") (pinfunction "IOB1_12") (pintype "bidirectional"))
    )
    (net (code "80") (name "unconnected-(D5-IOB2-Pad11)") (class "Default")
      (node (ref "D5") (pin "11") (pinfunction "IOB2_11") (pintype "bidirectional"))
    )
    (net (code "81") (name "unconnected-(D5-IOB3-Pad10)") (class "Default")
      (node (ref "D5") (pin "10") (pinfunction "IOB3_10") (pintype "bidirectional"))
    )
    (net (code "82") (name "unconnected-(D5-IOB4-Pad9)") (class "Default")
      (node (ref "D5") (pin "9") (pinfunction "IOB4_9") (pintype "bidirectional"))
    )
    (net (code "83") (name "unconnected-(D5-IOB5-Pad8)") (class "Default")
      (node (ref "D5") (pin "8") (pinfunction "IOB5_8") (pintype "bidirectional"))
    )
    (net (code "84") (name "unconnected-(D5-IOB6-Pad7)") (class "Default")
      (node (ref "D5") (pin "7") (pinfunction "IOB6_7") (pintype "bidirectional"))
    )
    (net (code "85") (name "unconnected-(D5-IOB7-Pad6)") (class "Default")
      (node (ref "D5") (pin "6") (pinfunction "IOB7_6") (pintype "bidirectional"))
    )
    (net (code "86") (name "unconnected-(D5-TST1-Pad39)") (class "Default")
      (node (ref "D5") (pin "39") (pinfunction "TST1_39") (pintype "passive"))
    )
    (net (code "87") (name "unconnected-(D5-n.c.-Pad2)") (class "Default")
      (node (ref "D5") (pin "2") (pinfunction "n.c._2") (pintype "passive"))
    )
    (net (code "88") (name "unconnected-(D5-n.c.-Pad5)") (class "Default")
      (node (ref "D5") (pin "5") (pinfunction "n.c._5") (pintype "passive"))
    )
    (net (code "89") (name "unconnected-(U1-RFB-Pad16)") (class "Default")
      (node (ref "U1") (pin "16") (pinfunction "RFB_16") (pintype "input"))
    )
  )
)
